# x21_jumper.net
KiCad netlist of a schematic drawn in EAGLE
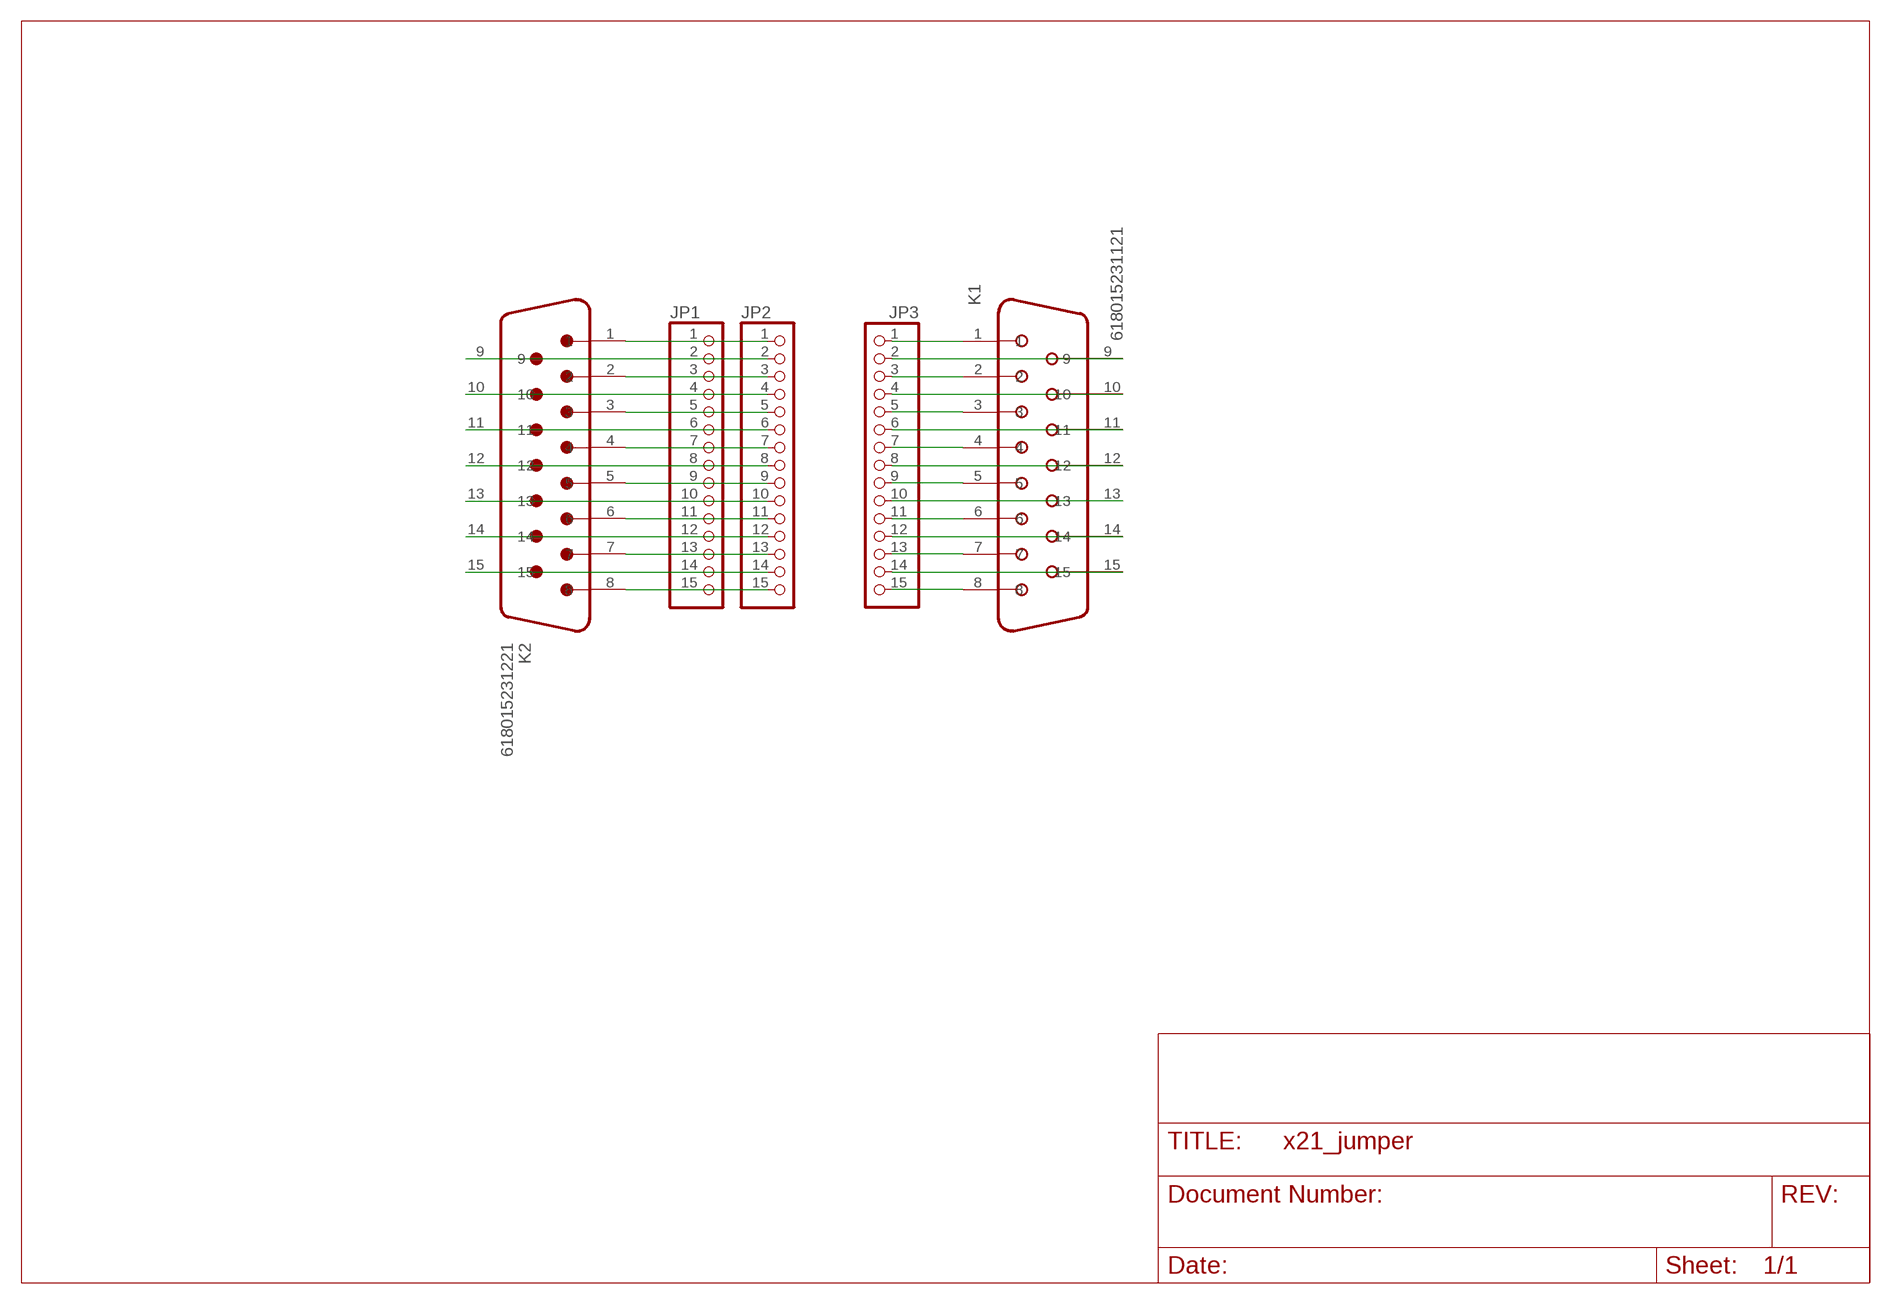
[diagram p0: schematic, sheet 1]

(export (version "E")
  (design (tool "Eeschema 10.0.6"))
  (components
    (comp (ref "JP1")
      (value "PINHD-1X15")
      (footprint "eagle-import:1X15")
      (libsource (lib "eagle-import") (part "PINHD-1X15"))
    )
    (comp (ref "JP2")
      (value "PINHD-1X15")
      (footprint "eagle-import:1X15")
      (libsource (lib "eagle-import") (part "PINHD-1X15"))
    )
    (comp (ref "JP3")
      (value "PINHD-1X15")
      (footprint "eagle-import:1X15")
      (libsource (lib "eagle-import") (part "PINHD-1X15"))
    )
    (comp (ref "K1")
      (value "618015231121")
      (footprint "eagle-import:618015231121")
      (libsource (lib "eagle-import") (part "618015231121"))
    )
    (comp (ref "K2")
      (value "618015231221")
      (footprint "eagle-import:618015231221")
      (libsource (lib "eagle-import") (part "618015231221"))
    )
  )
  (nets
    (net (code "1") (name "Net-(JP1-Pad1)") (class "Default")
      (node (ref "JP1") (pin "1") (pinfunction "1_1") (pintype "passive"))
      (node (ref "JP2") (pin "1") (pinfunction "1_1") (pintype "passive"))
      (node (ref "K2") (pin "1") (pinfunction "1_1") (pintype "bidirectional"))
    )
    (net (code "2") (name "Net-(JP1-Pad2)") (class "Default")
      (node (ref "JP1") (pin "2") (pinfunction "2_2") (pintype "passive"))
      (node (ref "JP2") (pin "2") (pinfunction "2_2") (pintype "passive"))
      (node (ref "K2") (pin "9") (pinfunction "9_9") (pintype "bidirectional"))
    )
    (net (code "3") (name "Net-(JP1-Pad3)") (class "Default")
      (node (ref "JP1") (pin "3") (pinfunction "3_3") (pintype "passive"))
      (node (ref "JP2") (pin "3") (pinfunction "3_3") (pintype "passive"))
      (node (ref "K2") (pin "2") (pinfunction "2_2") (pintype "bidirectional"))
    )
    (net (code "4") (name "Net-(JP1-Pad4)") (class "Default")
      (node (ref "JP1") (pin "4") (pinfunction "4_4") (pintype "passive"))
      (node (ref "JP2") (pin "4") (pinfunction "4_4") (pintype "passive"))
      (node (ref "K2") (pin "10") (pinfunction "10_10") (pintype "bidirectional"))
    )
    (net (code "5") (name "Net-(JP1-Pad5)") (class "Default")
      (node (ref "JP1") (pin "5") (pinfunction "5_5") (pintype "passive"))
      (node (ref "JP2") (pin "5") (pinfunction "5_5") (pintype "passive"))
      (node (ref "K2") (pin "3") (pinfunction "3_3") (pintype "bidirectional"))
    )
    (net (code "6") (name "Net-(JP1-Pad6)") (class "Default")
      (node (ref "JP1") (pin "6") (pinfunction "6_6") (pintype "passive"))
      (node (ref "JP2") (pin "6") (pinfunction "6_6") (pintype "passive"))
      (node (ref "K2") (pin "11") (pinfunction "11_11") (pintype "bidirectional"))
    )
    (net (code "7") (name "Net-(JP1-Pad7)") (class "Default")
      (node (ref "JP1") (pin "7") (pinfunction "7_7") (pintype "passive"))
      (node (ref "JP2") (pin "7") (pinfunction "7_7") (pintype "passive"))
      (node (ref "K2") (pin "4") (pinfunction "4_4") (pintype "bidirectional"))
    )
    (net (code "8") (name "Net-(JP1-Pad8)") (class "Default")
      (node (ref "JP1") (pin "8") (pinfunction "8_8") (pintype "passive"))
      (node (ref "JP2") (pin "8") (pinfunction "8_8") (pintype "passive"))
      (node (ref "K2") (pin "12") (pinfunction "12_12") (pintype "bidirectional"))
    )
    (net (code "9") (name "Net-(JP1-Pad9)") (class "Default")
      (node (ref "JP1") (pin "9") (pinfunction "9_9") (pintype "passive"))
      (node (ref "JP2") (pin "9") (pinfunction "9_9") (pintype "passive"))
      (node (ref "K2") (pin "5") (pinfunction "5_5") (pintype "bidirectional"))
    )
    (net (code "10") (name "Net-(JP1-Pad10)") (class "Default")
      (node (ref "JP1") (pin "10") (pinfunction "10_10") (pintype "passive"))
      (node (ref "JP2") (pin "10") (pinfunction "10_10") (pintype "passive"))
      (node (ref "K2") (pin "13") (pinfunction "13_13") (pintype "bidirectional"))
    )
    (net (code "11") (name "Net-(JP1-Pad11)") (class "Default")
      (node (ref "JP1") (pin "11") (pinfunction "11_11") (pintype "passive"))
      (node (ref "JP2") (pin "11") (pinfunction "11_11") (pintype "passive"))
      (node (ref "K2") (pin "6") (pinfunction "6_6") (pintype "bidirectional"))
    )
    (net (code "12") (name "Net-(JP1-Pad12)") (class "Default")
      (node (ref "JP1") (pin "12") (pinfunction "12_12") (pintype "passive"))
      (node (ref "JP2") (pin "12") (pinfunction "12_12") (pintype "passive"))
      (node (ref "K2") (pin "14") (pinfunction "14_14") (pintype "bidirectional"))
    )
    (net (code "13") (name "Net-(JP1-Pad13)") (class "Default")
      (node (ref "JP1") (pin "13") (pinfunction "13_13") (pintype "passive"))
      (node (ref "JP2") (pin "13") (pinfunction "13_13") (pintype "passive"))
      (node (ref "K2") (pin "7") (pinfunction "7_7") (pintype "bidirectional"))
    )
    (net (code "14") (name "Net-(JP1-Pad14)") (class "Default")
      (node (ref "JP1") (pin "14") (pinfunction "14_14") (pintype "passive"))
      (node (ref "JP2") (pin "14") (pinfunction "14_14") (pintype "passive"))
      (node (ref "K2") (pin "15") (pinfunction "15_15") (pintype "bidirectional"))
    )
    (net (code "15") (name "Net-(JP1-Pad15)") (class "Default")
      (node (ref "JP1") (pin "15") (pinfunction "15_15") (pintype "passive"))
      (node (ref "JP2") (pin "15") (pinfunction "15_15") (pintype "passive"))
      (node (ref "K2") (pin "8") (pinfunction "8_8") (pintype "bidirectional"))
    )
    (net (code "16") (name "Net-(JP3-Pad1)") (class "Default")
      (node (ref "JP3") (pin "1") (pinfunction "1_1") (pintype "passive"))
      (node (ref "K1") (pin "1") (pinfunction "1_1") (pintype "bidirectional"))
    )
    (net (code "17") (name "Net-(JP3-Pad2)") (class "Default")
      (node (ref "JP3") (pin "2") (pinfunction "2_2") (pintype "passive"))
      (node (ref "K1") (pin "9") (pinfunction "9_9") (pintype "bidirectional"))
    )
    (net (code "18") (name "Net-(JP3-Pad3)") (class "Default")
      (node (ref "JP3") (pin "3") (pinfunction "3_3") (pintype "passive"))
      (node (ref "K1") (pin "2") (pinfunction "2_2") (pintype "bidirectional"))
    )
    (net (code "19") (name "Net-(JP3-Pad4)") (class "Default")
      (node (ref "JP3") (pin "4") (pinfunction "4_4") (pintype "passive"))
      (node (ref "K1") (pin "10") (pinfunction "10_10") (pintype "bidirectional"))
    )
    (net (code "20") (name "Net-(JP3-Pad5)") (class "Default")
      (node (ref "JP3") (pin "5") (pinfunction "5_5") (pintype "passive"))
      (node (ref "K1") (pin "3") (pinfunction "3_3") (pintype "bidirectional"))
    )
    (net (code "21") (name "Net-(JP3-Pad6)") (class "Default")
      (node (ref "JP3") (pin "6") (pinfunction "6_6") (pintype "passive"))
      (node (ref "K1") (pin "11") (pinfunction "11_11") (pintype "bidirectional"))
    )
    (net (code "22") (name "Net-(JP3-Pad7)") (class "Default")
      (node (ref "JP3") (pin "7") (pinfunction "7_7") (pintype "passive"))
      (node (ref "K1") (pin "4") (pinfunction "4_4") (pintype "bidirectional"))
    )
    (net (code "23") (name "Net-(JP3-Pad8)") (class "Default")
      (node (ref "JP3") (pin "8") (pinfunction "8_8") (pintype "passive"))
      (node (ref "K1") (pin "12") (pinfunction "12_12") (pintype "bidirectional"))
    )
    (net (code "24") (name "Net-(JP3-Pad9)") (class "Default")
      (node (ref "JP3") (pin "9") (pinfunction "9_9") (pintype "passive"))
      (node (ref "K1") (pin "5") (pinfunction "5_5") (pintype "bidirectional"))
    )
    (net (code "25") (name "Net-(JP3-Pad10)") (class "Default")
      (node (ref "JP3") (pin "10") (pinfunction "10_10") (pintype "passive"))
      (node (ref "K1") (pin "13") (pinfunction "13_13") (pintype "bidirectional"))
    )
    (net (code "26") (name "Net-(JP3-Pad11)") (class "Default")
      (node (ref "JP3") (pin "11") (pinfunction "11_11") (pintype "passive"))
      (node (ref "K1") (pin "6") (pinfunction "6_6") (pintype "bidirectional"))
    )
    (net (code "27") (name "Net-(JP3-Pad12)") (class "Default")
      (node (ref "JP3") (pin "12") (pinfunction "12_12") (pintype "passive"))
      (node (ref "K1") (pin "14") (pinfunction "14_14") (pintype "bidirectional"))
    )
    (net (code "28") (name "Net-(JP3-Pad13)") (class "Default")
      (node (ref "JP3") (pin "13") (pinfunction "13_13") (pintype "passive"))
      (node (ref "K1") (pin "7") (pinfunction "7_7") (pintype "bidirectional"))
    )
    (net (code "29") (name "Net-(JP3-Pad14)") (class "Default")
      (node (ref "JP3") (pin "14") (pinfunction "14_14") (pintype "passive"))
      (node (ref "K1") (pin "15") (pinfunction "15_15") (pintype "bidirectional"))
    )
    (net (code "30") (name "Net-(JP3-Pad15)") (class "Default")
      (node (ref "JP3") (pin "15") (pinfunction "15_15") (pintype "passive"))
      (node (ref "K1") (pin "8") (pinfunction "8_8") (pintype "bidirectional"))
    )
  )
)
